# STM32SC1.net
KiCad netlist of a schematic drawn in EAGLE
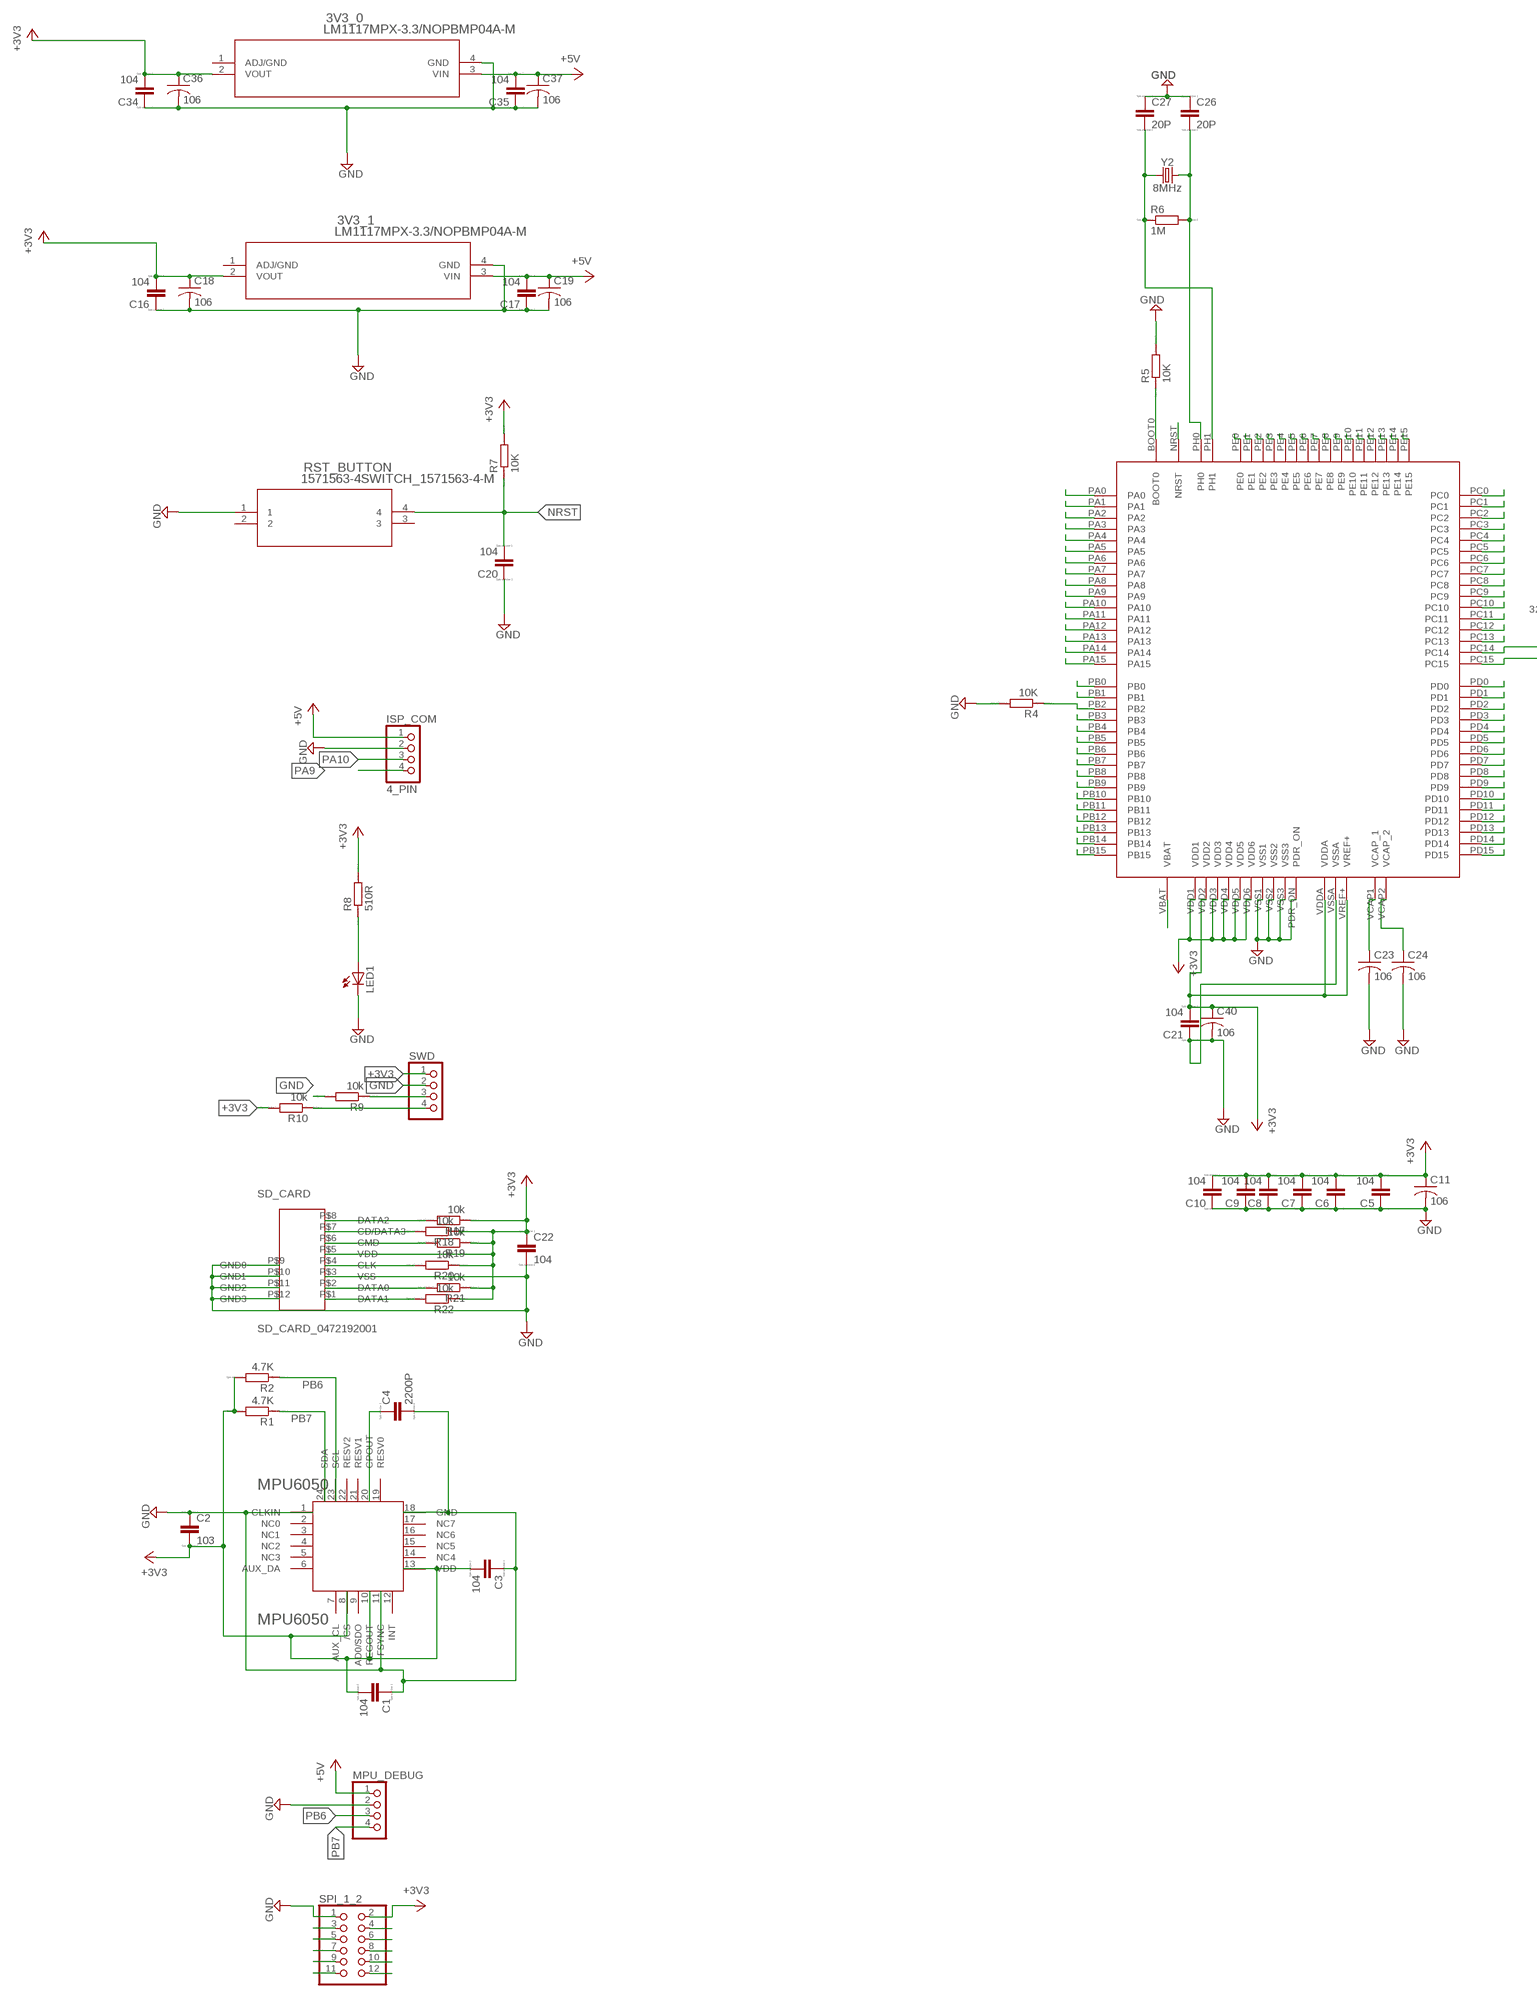
[diagram p0: schematic, sheet 1, part 1 of 2]
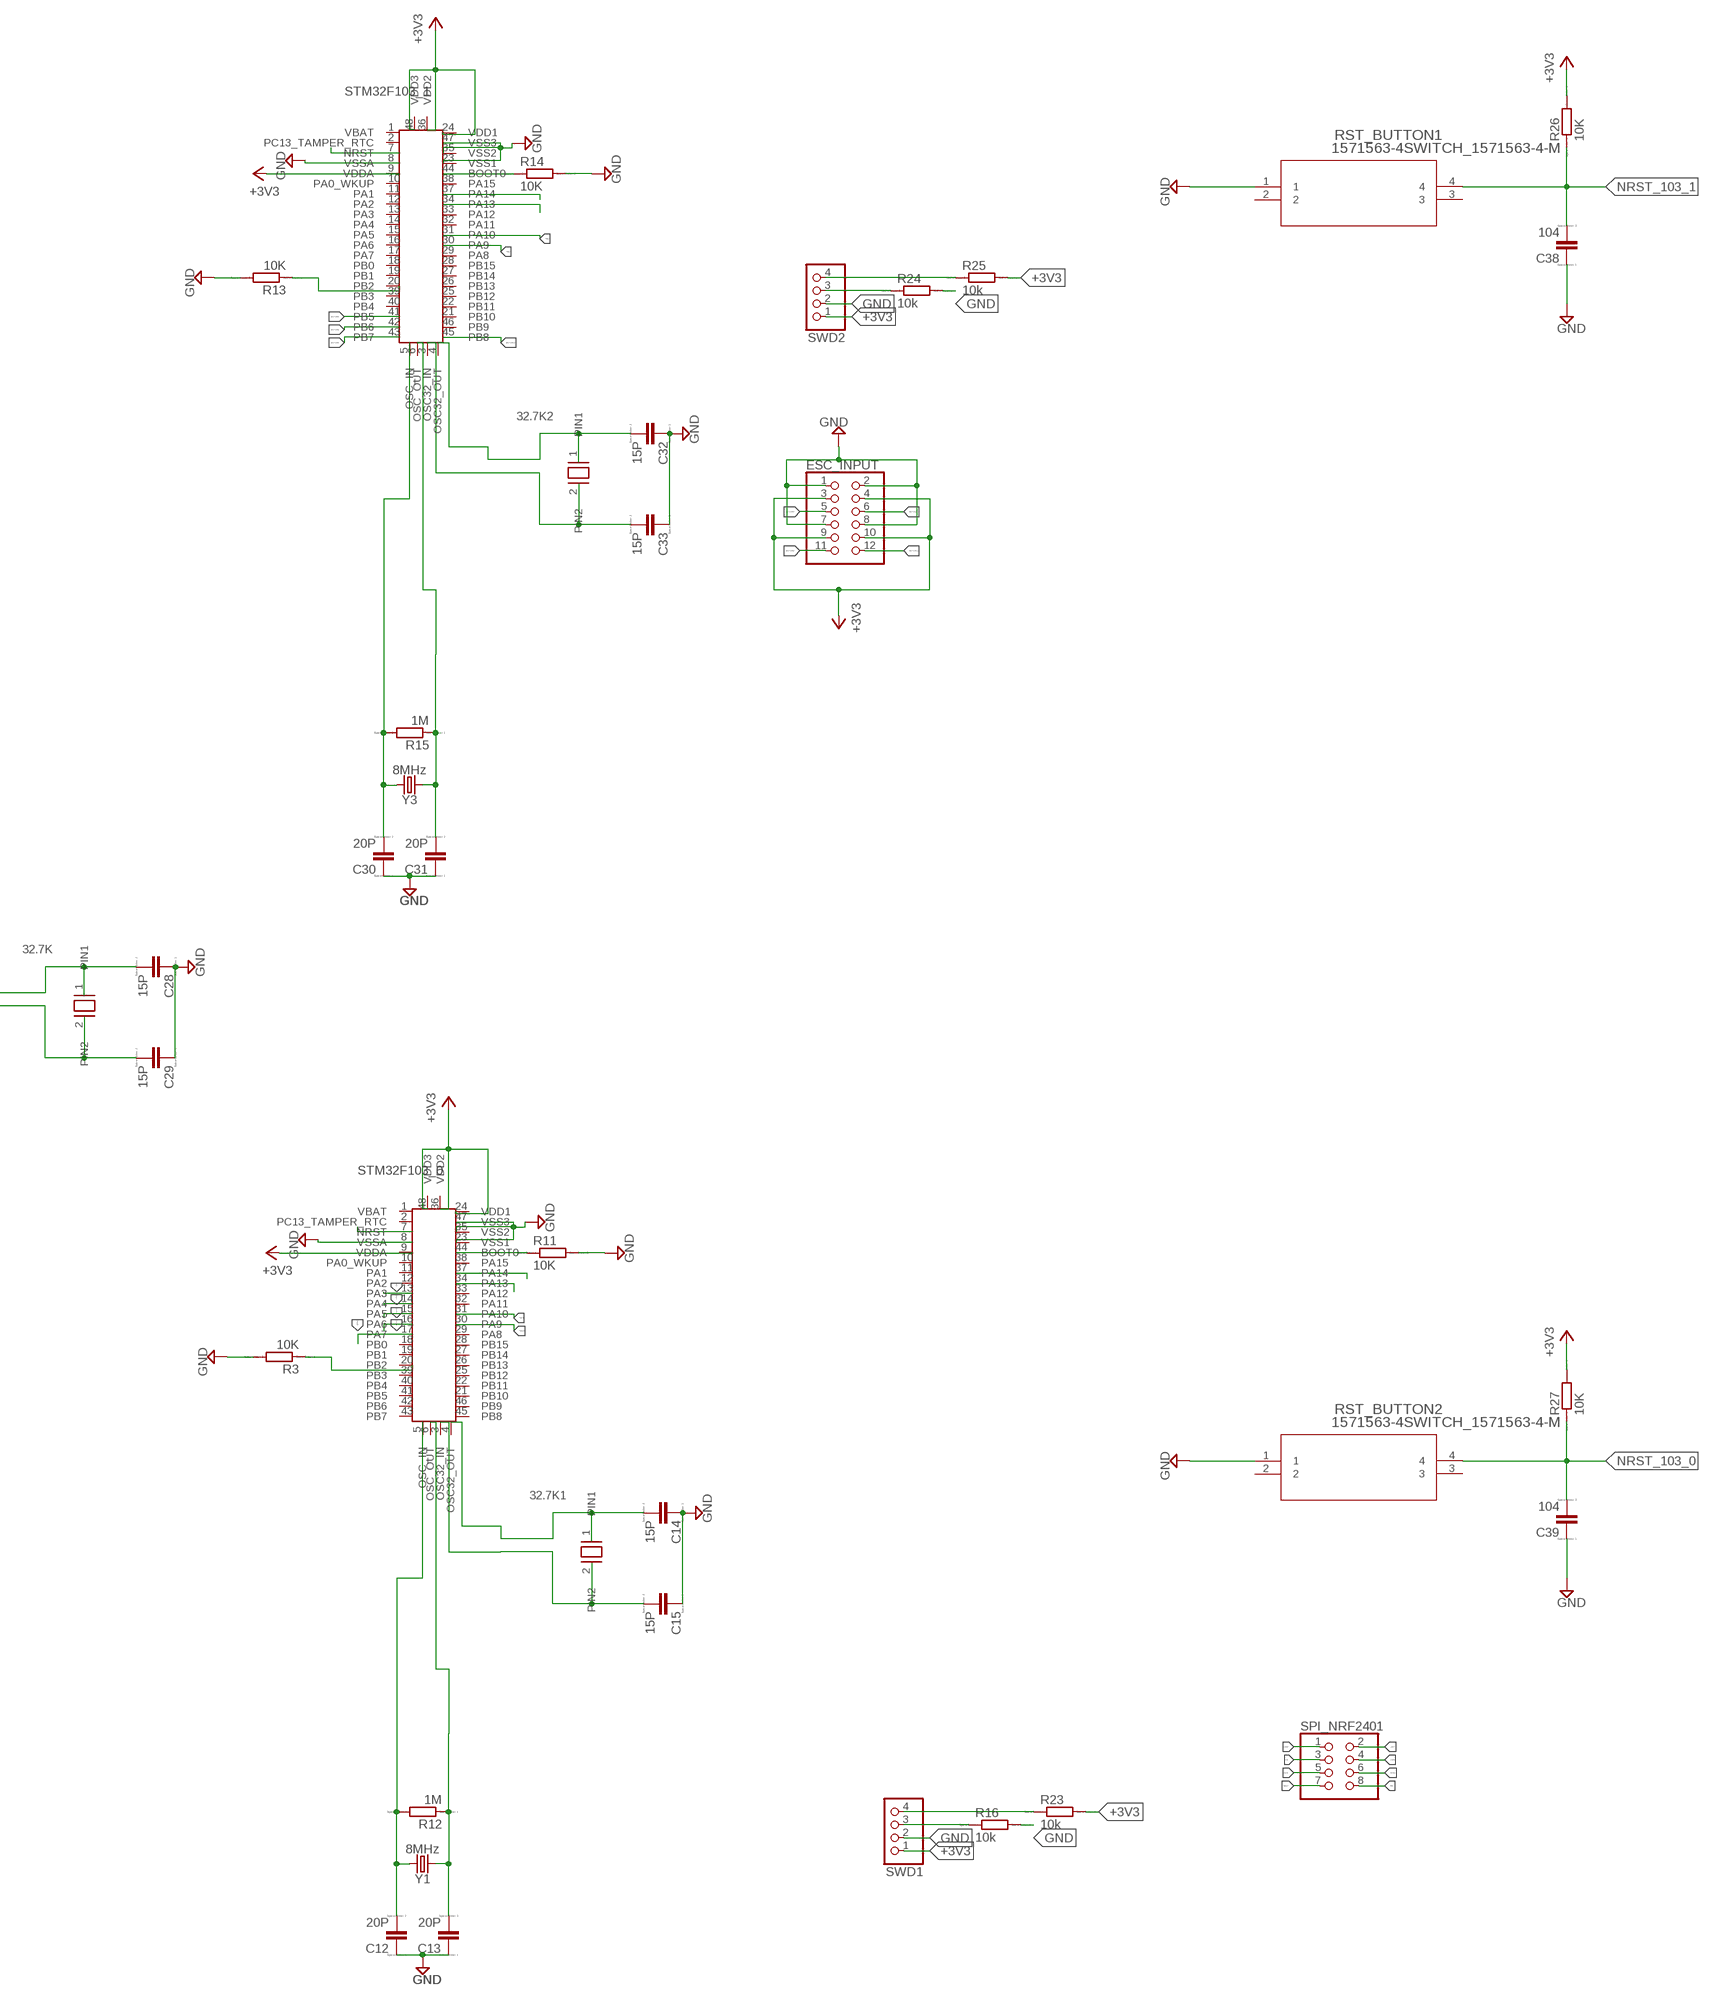
[diagram p1: schematic, sheet 1, part 2 of 2]

(export (version "E")
  (design (tool "Eeschema 10.0.6"))
  (components
    (comp (ref "3V3_0")
      (value "LM1117MPX-3.3/NOPBMP04A-M")
      (footprint "eagle-import:MP04A-M")
      (fields (field (name "MANUFACTURER_PART_NUMBER") "LM1117MPX3.3NOPB"))
      (libsource (lib "eagle-import") (part "LM1117MPX-3.3/NOPBMP04A-M"))
    )
    (comp (ref "3V3_1")
      (value "LM1117MPX-3.3/NOPBMP04A-M")
      (footprint "eagle-import:MP04A-M")
      (fields (field (name "MANUFACTURER_PART_NUMBER") "LM1117MPX3.3NOPB"))
      (libsource (lib "eagle-import") (part "LM1117MPX-3.3/NOPBMP04A-M"))
    )
    (comp (ref "32.7K")
      (value "CM315D")
      (footprint "eagle-import:CM315D_32.7K")
      (libsource (lib "eagle-import") (part "CM315D"))
    )
    (comp (ref "32.7K1")
      (value "CM315D")
      (footprint "eagle-import:CM315D_32.7K")
      (libsource (lib "eagle-import") (part "CM315D"))
    )
    (comp (ref "32.7K2")
      (value "CM315D")
      (footprint "eagle-import:CM315D_32.7K")
      (libsource (lib "eagle-import") (part "CM315D"))
    )
    (comp (ref "C1")
      (value "104")
      (footprint "eagle-import:C0603")
      (libsource (lib "eagle-import") (part "CC0603"))
    )
    (comp (ref "C2")
      (value "103")
      (footprint "eagle-import:C0603")
      (libsource (lib "eagle-import") (part "CC0603"))
    )
    (comp (ref "C3")
      (value "104")
      (footprint "eagle-import:C0603")
      (libsource (lib "eagle-import") (part "CC0603"))
    )
    (comp (ref "C4")
      (value "2200P")
      (footprint "eagle-import:C0603")
      (libsource (lib "eagle-import") (part "CC0603"))
    )
    (comp (ref "C5")
      (value "104")
      (footprint "eagle-import:C0603")
      (libsource (lib "eagle-import") (part "CC0603"))
    )
    (comp (ref "C6")
      (value "104")
      (footprint "eagle-import:C0603")
      (libsource (lib "eagle-import") (part "CC0603"))
    )
    (comp (ref "C7")
      (value "104")
      (footprint "eagle-import:C0603")
      (libsource (lib "eagle-import") (part "CC0603"))
    )
    (comp (ref "C8")
      (value "104")
      (footprint "eagle-import:C0603")
      (libsource (lib "eagle-import") (part "CC0603"))
    )
    (comp (ref "C9")
      (value "104")
      (footprint "eagle-import:C0603")
      (libsource (lib "eagle-import") (part "CC0603"))
    )
    (comp (ref "C10")
      (value "104")
      (footprint "eagle-import:C0603")
      (libsource (lib "eagle-import") (part "CC0603"))
    )
    (comp (ref "C11")
      (value "106")
      (footprint "eagle-import:C0805")
      (libsource (lib "eagle-import") (part "C-USC0805"))
    )
    (comp (ref "C12")
      (value "20P")
      (footprint "eagle-import:C0603")
      (libsource (lib "eagle-import") (part "CC0603"))
    )
    (comp (ref "C13")
      (value "20P")
      (footprint "eagle-import:C0603")
      (libsource (lib "eagle-import") (part "CC0603"))
    )
    (comp (ref "C14")
      (value "15P")
      (footprint "eagle-import:C0603")
      (libsource (lib "eagle-import") (part "CC0603"))
    )
    (comp (ref "C15")
      (value "15P")
      (footprint "eagle-import:C0603")
      (libsource (lib "eagle-import") (part "CC0603"))
    )
    (comp (ref "C16")
      (value "104")
      (footprint "eagle-import:C0603")
      (libsource (lib "eagle-import") (part "CC0603"))
    )
    (comp (ref "C17")
      (value "104")
      (footprint "eagle-import:C0603")
      (libsource (lib "eagle-import") (part "CC0603"))
    )
    (comp (ref "C18")
      (value "106")
      (footprint "eagle-import:C0805")
      (libsource (lib "eagle-import") (part "C-USC0805"))
    )
    (comp (ref "C19")
      (value "106")
      (footprint "eagle-import:C0805")
      (libsource (lib "eagle-import") (part "C-USC0805"))
    )
    (comp (ref "C20")
      (value "104")
      (footprint "eagle-import:C0603")
      (libsource (lib "eagle-import") (part "CC0603"))
    )
    (comp (ref "C21")
      (value "104")
      (footprint "eagle-import:C0603")
      (libsource (lib "eagle-import") (part "CC0603"))
    )
    (comp (ref "C22")
      (value "104")
      (footprint "eagle-import:C0603")
      (libsource (lib "eagle-import") (part "CC0603"))
    )
    (comp (ref "C23")
      (value "106")
      (footprint "eagle-import:C0805")
      (libsource (lib "eagle-import") (part "C-USC0805"))
    )
    (comp (ref "C24")
      (value "106")
      (footprint "eagle-import:C0805")
      (libsource (lib "eagle-import") (part "C-USC0805"))
    )
    (comp (ref "C26")
      (value "20P")
      (footprint "eagle-import:C0603")
      (libsource (lib "eagle-import") (part "CC0603"))
    )
    (comp (ref "C27")
      (value "20P")
      (footprint "eagle-import:C0603")
      (libsource (lib "eagle-import") (part "CC0603"))
    )
    (comp (ref "C28")
      (value "15P")
      (footprint "eagle-import:C0603")
      (libsource (lib "eagle-import") (part "CC0603"))
    )
    (comp (ref "C29")
      (value "15P")
      (footprint "eagle-import:C0603")
      (libsource (lib "eagle-import") (part "CC0603"))
    )
    (comp (ref "C30")
      (value "20P")
      (footprint "eagle-import:C0603")
      (libsource (lib "eagle-import") (part "CC0603"))
    )
    (comp (ref "C31")
      (value "20P")
      (footprint "eagle-import:C0603")
      (libsource (lib "eagle-import") (part "CC0603"))
    )
    (comp (ref "C32")
      (value "15P")
      (footprint "eagle-import:C0603")
      (libsource (lib "eagle-import") (part "CC0603"))
    )
    (comp (ref "C33")
      (value "15P")
      (footprint "eagle-import:C0603")
      (libsource (lib "eagle-import") (part "CC0603"))
    )
    (comp (ref "C34")
      (value "104")
      (footprint "eagle-import:C0603")
      (libsource (lib "eagle-import") (part "CC0603"))
    )
    (comp (ref "C35")
      (value "104")
      (footprint "eagle-import:C0603")
      (libsource (lib "eagle-import") (part "CC0603"))
    )
    (comp (ref "C36")
      (value "106")
      (footprint "eagle-import:C0805")
      (libsource (lib "eagle-import") (part "C-USC0805"))
    )
    (comp (ref "C37")
      (value "106")
      (footprint "eagle-import:C0805")
      (libsource (lib "eagle-import") (part "C-USC0805"))
    )
    (comp (ref "C38")
      (value "104")
      (footprint "eagle-import:C0603")
      (libsource (lib "eagle-import") (part "CC0603"))
    )
    (comp (ref "C39")
      (value "104")
      (footprint "eagle-import:C0603")
      (libsource (lib "eagle-import") (part "CC0603"))
    )
    (comp (ref "C40")
      (value "106")
      (footprint "eagle-import:C0805")
      (libsource (lib "eagle-import") (part "C-USC0805"))
    )
    (comp (ref "ESC_INPUT")
      (value "PINHD-2X6/90")
      (footprint "eagle-import:2X06_90")
      (libsource (lib "eagle-import") (part "PINHD-2X6/90"))
    )
    (comp (ref "ISP_COM")
      (value "4_PIN")
      (footprint "eagle-import:1X04")
      (libsource (lib "eagle-import") (part "PINHD-1X4"))
    )
    (comp (ref "LED1")
      (value "LEDCHIPLED_0805")
      (footprint "eagle-import:CHIPLED_0805")
      (libsource (lib "eagle-import") (part "LEDCHIPLED_0805"))
    )
    (comp (ref "MPU6050")
      (value "MPU6050")
      (footprint "eagle-import:MPU6050")
      (libsource (lib "eagle-import") (part "MPU6050"))
    )
    (comp (ref "MPU_DEBUG")
      (value "PINHD-1X4")
      (footprint "eagle-import:1X04")
      (libsource (lib "eagle-import") (part "PINHD-1X4"))
    )
    (comp (ref "R1")
      (value "4.7K")
      (footprint "eagle-import:R0603")
      (libsource (lib "eagle-import") (part "RR0603"))
    )
    (comp (ref "R2")
      (value "4.7K")
      (footprint "eagle-import:R0603")
      (libsource (lib "eagle-import") (part "RR0603"))
    )
    (comp (ref "R3")
      (value "10K")
      (footprint "eagle-import:R0603")
      (libsource (lib "eagle-import") (part "RR0603"))
    )
    (comp (ref "R4")
      (value "10K")
      (footprint "eagle-import:R0603")
      (libsource (lib "eagle-import") (part "RR0603"))
    )
    (comp (ref "R5")
      (value "10K")
      (footprint "eagle-import:R0603")
      (libsource (lib "eagle-import") (part "RR0603"))
    )
    (comp (ref "R6")
      (value "1M")
      (footprint "eagle-import:R0603")
      (libsource (lib "eagle-import") (part "RR0603"))
    )
    (comp (ref "R7")
      (value "10K")
      (footprint "eagle-import:R0603")
      (libsource (lib "eagle-import") (part "RR0603"))
    )
    (comp (ref "R8")
      (value "510R")
      (footprint "eagle-import:R0603")
      (libsource (lib "eagle-import") (part "RR0603"))
    )
    (comp (ref "R9")
      (value "10k")
      (footprint "eagle-import:R0603")
      (libsource (lib "eagle-import") (part "RR0603"))
    )
    (comp (ref "R10")
      (value "10k")
      (footprint "eagle-import:R0603")
      (libsource (lib "eagle-import") (part "RR0603"))
    )
    (comp (ref "R11")
      (value "10K")
      (footprint "eagle-import:R0603")
      (libsource (lib "eagle-import") (part "RR0603"))
    )
    (comp (ref "R12")
      (value "1M")
      (footprint "eagle-import:R0603")
      (libsource (lib "eagle-import") (part "RR0603"))
    )
    (comp (ref "R13")
      (value "10K")
      (footprint "eagle-import:R0603")
      (libsource (lib "eagle-import") (part "RR0603"))
    )
    (comp (ref "R14")
      (value "10K")
      (footprint "eagle-import:R0603")
      (libsource (lib "eagle-import") (part "RR0603"))
    )
    (comp (ref "R15")
      (value "1M")
      (footprint "eagle-import:R0603")
      (libsource (lib "eagle-import") (part "RR0603"))
    )
    (comp (ref "R16")
      (value "10k")
      (footprint "eagle-import:R0603")
      (libsource (lib "eagle-import") (part "RR0603"))
    )
    (comp (ref "R17")
      (value "10k")
      (footprint "eagle-import:R0603")
      (libsource (lib "eagle-import") (part "RR0603"))
    )
    (comp (ref "R18")
      (value "10k")
      (footprint "eagle-import:R0603")
      (libsource (lib "eagle-import") (part "RR0603"))
    )
    (comp (ref "R19")
      (value "10k")
      (footprint "eagle-import:R0603")
      (libsource (lib "eagle-import") (part "RR0603"))
    )
    (comp (ref "R20")
      (value "10k")
      (footprint "eagle-import:R0603")
      (libsource (lib "eagle-import") (part "RR0603"))
    )
    (comp (ref "R21")
      (value "10k")
      (footprint "eagle-import:R0603")
      (libsource (lib "eagle-import") (part "RR0603"))
    )
    (comp (ref "R22")
      (value "10k")
      (footprint "eagle-import:R0603")
      (libsource (lib "eagle-import") (part "RR0603"))
    )
    (comp (ref "R23")
      (value "10k")
      (footprint "eagle-import:R0603")
      (libsource (lib "eagle-import") (part "RR0603"))
    )
    (comp (ref "R24")
      (value "10k")
      (footprint "eagle-import:R0603")
      (libsource (lib "eagle-import") (part "RR0603"))
    )
    (comp (ref "R25")
      (value "10k")
      (footprint "eagle-import:R0603")
      (libsource (lib "eagle-import") (part "RR0603"))
    )
    (comp (ref "R26")
      (value "10K")
      (footprint "eagle-import:R0603")
      (libsource (lib "eagle-import") (part "RR0603"))
    )
    (comp (ref "R27")
      (value "10K")
      (footprint "eagle-import:R0603")
      (libsource (lib "eagle-import") (part "RR0603"))
    )
    (comp (ref "RST_BUTTON")
      (value "1571563-4SWITCH_1571563-4-M")
      (footprint "eagle-import:SWITCH_1571563-4-M")
      (fields (field (name "MANUFACTURER_PART_NUMBER") "15715634"))
      (libsource (lib "eagle-import") (part "1571563-4SWITCH_1571563-4-M"))
    )
    (comp (ref "RST_BUTTON1")
      (value "1571563-4SWITCH_1571563-4-M")
      (footprint "eagle-import:SWITCH_1571563-4-M")
      (fields (field (name "MANUFACTURER_PART_NUMBER") "15715634"))
      (libsource (lib "eagle-import") (part "1571563-4SWITCH_1571563-4-M"))
    )
    (comp (ref "RST_BUTTON2")
      (value "1571563-4SWITCH_1571563-4-M")
      (footprint "eagle-import:SWITCH_1571563-4-M")
      (fields (field (name "MANUFACTURER_PART_NUMBER") "15715634"))
      (libsource (lib "eagle-import") (part "1571563-4SWITCH_1571563-4-M"))
    )
    (comp (ref "SD_CARD")
      (value "SD_CARD_0472192001")
      (footprint "eagle-import:0472192001")
      (libsource (lib "eagle-import") (part "SD_CARD_0472192001"))
    )
    (comp (ref "SPI_1_2")
      (value "PINHD-2X6/90")
      (footprint "eagle-import:2X06_90")
      (libsource (lib "eagle-import") (part "PINHD-2X6/90"))
    )
    (comp (ref "SPI_NRF2401")
      (value "PINHD-2X4")
      (footprint "eagle-import:2X04")
      (libsource (lib "eagle-import") (part "PINHD-2X4"))
    )
    (comp (ref "STM32F103_0")
      (value "STM32F103C8T6")
      (footprint "eagle-import:STM32103C8T6_LQFP48")
      (libsource (lib "eagle-import") (part "STM32F103C8T6"))
    )
    (comp (ref "STM32F103_1")
      (value "STM32F103C8T6")
      (footprint "eagle-import:STM32103C8T6_LQFP48")
      (libsource (lib "eagle-import") (part "STM32F103C8T6"))
    )
    (comp (ref "SWD")
      (value "PINHD-1X4")
      (footprint "eagle-import:1X04")
      (libsource (lib "eagle-import") (part "PINHD-1X4"))
    )
    (comp (ref "SWD1")
      (value "PINHD-1X4")
      (footprint "eagle-import:1X04")
      (libsource (lib "eagle-import") (part "PINHD-1X4"))
    )
    (comp (ref "SWD2")
      (value "PINHD-1X4")
      (footprint "eagle-import:1X04")
      (libsource (lib "eagle-import") (part "PINHD-1X4"))
    )
    (comp (ref "U$1")
      (value "STM32F4V_100PIN_GENERIC")
      (footprint "eagle-import:LQFP100")
      (libsource (lib "eagle-import") (part "STM32F4V_100PIN_GENERIC"))
    )
    (comp (ref "Y1")
      (value "8MHz")
      (footprint "eagle-import:HC49UP")
      (libsource (lib "eagle-import") (part "CRYSTAL-8MHZSMD-HC49UP"))
    )
    (comp (ref "Y2")
      (value "8MHz")
      (footprint "eagle-import:HC49UP")
      (libsource (lib "eagle-import") (part "CRYSTAL-8MHZSMD-HC49UP"))
    )
    (comp (ref "Y3")
      (value "8MHz")
      (footprint "eagle-import:HC49UP")
      (libsource (lib "eagle-import") (part "CRYSTAL-8MHZSMD-HC49UP"))
    )
  )
  (nets
    (net (code "1") (name "+3V3") (class "Default")
      (node (ref "3V3_0") (pin "2") (pinfunction "VOUT_2") (pintype "passive"))
      (node (ref "3V3_1") (pin "2") (pinfunction "VOUT_2") (pintype "passive"))
      (node (ref "C1") (pin "2") (pinfunction "2_2") (pintype "passive"))
      (node (ref "C10") (pin "2") (pinfunction "2_2") (pintype "passive"))
      (node (ref "C11") (pin "1") (pinfunction "1_1") (pintype "passive"))
      (node (ref "C16") (pin "2") (pinfunction "2_2") (pintype "passive"))
      (node (ref "C18") (pin "1") (pinfunction "1_1") (pintype "passive"))
      (node (ref "C2") (pin "2") (pinfunction "2_2") (pintype "passive"))
      (node (ref "C21") (pin "2") (pinfunction "2_2") (pintype "passive"))
      (node (ref "C22") (pin "1") (pinfunction "1_1") (pintype "passive"))
      (node (ref "C3") (pin "2") (pinfunction "2_2") (pintype "passive"))
      (node (ref "C34") (pin "2") (pinfunction "2_2") (pintype "passive"))
      (node (ref "C36") (pin "1") (pinfunction "1_1") (pintype "passive"))
      (node (ref "C40") (pin "1") (pinfunction "1_1") (pintype "passive"))
      (node (ref "C5") (pin "2") (pinfunction "2_2") (pintype "passive"))
      (node (ref "C6") (pin "2") (pinfunction "2_2") (pintype "passive"))
      (node (ref "C7") (pin "2") (pinfunction "2_2") (pintype "passive"))
      (node (ref "C8") (pin "2") (pinfunction "2_2") (pintype "passive"))
      (node (ref "C9") (pin "2") (pinfunction "2_2") (pintype "passive"))
      (node (ref "ESC_INPUT") (pin "10") (pinfunction "10_10") (pintype "passive"))
      (node (ref "ESC_INPUT") (pin "3") (pinfunction "3_3") (pintype "passive"))
      (node (ref "ESC_INPUT") (pin "4") (pinfunction "4_4") (pintype "passive"))
      (node (ref "ESC_INPUT") (pin "9") (pinfunction "9_9") (pintype "passive"))
      (node (ref "MPU6050") (pin "10") (pinfunction "REGOUT_10") (pintype "bidirectional"))
      (node (ref "MPU6050") (pin "13") (pinfunction "VDD_13") (pintype "bidirectional"))
      (node (ref "MPU6050") (pin "8") (pinfunction "/CS_8") (pintype "bidirectional"))
      (node (ref "R1") (pin "2") (pinfunction "2_2") (pintype "passive"))
      (node (ref "R10") (pin "2") (pinfunction "2_2") (pintype "passive"))
      (node (ref "R17") (pin "1") (pinfunction "1_1") (pintype "passive"))
      (node (ref "R18") (pin "1") (pinfunction "1_1") (pintype "passive"))
      (node (ref "R19") (pin "1") (pinfunction "1_1") (pintype "passive"))
      (node (ref "R2") (pin "2") (pinfunction "2_2") (pintype "passive"))
      (node (ref "R20") (pin "1") (pinfunction "1_1") (pintype "passive"))
      (node (ref "R21") (pin "1") (pinfunction "1_1") (pintype "passive"))
      (node (ref "R22") (pin "1") (pinfunction "1_1") (pintype "passive"))
      (node (ref "R23") (pin "2") (pinfunction "2_2") (pintype "passive"))
      (node (ref "R25") (pin "2") (pinfunction "2_2") (pintype "passive"))
      (node (ref "R26") (pin "2") (pinfunction "2_2") (pintype "passive"))
      (node (ref "R27") (pin "2") (pinfunction "2_2") (pintype "passive"))
      (node (ref "R7") (pin "2") (pinfunction "2_2") (pintype "passive"))
      (node (ref "R8") (pin "2") (pinfunction "2_2") (pintype "passive"))
      (node (ref "SD_CARD") (pin "P$5") (pinfunction "VDD_P$5") (pintype "bidirectional"))
      (node (ref "SPI_1_2") (pin "2") (pinfunction "2_2") (pintype "passive"))
      (node (ref "SPI_NRF2401") (pin "2") (pinfunction "2_2") (pintype "passive"))
      (node (ref "STM32F103_0") (pin "24") (pinfunction "VDD1_24") (pintype "bidirectional"))
      (node (ref "STM32F103_0") (pin "36") (pinfunction "VDD2_36") (pintype "bidirectional"))
      (node (ref "STM32F103_0") (pin "48") (pinfunction "VDD3_48") (pintype "bidirectional"))
      (node (ref "STM32F103_0") (pin "9") (pinfunction "VDDA_9") (pintype "bidirectional"))
      (node (ref "STM32F103_1") (pin "24") (pinfunction "VDD1_24") (pintype "bidirectional"))
      (node (ref "STM32F103_1") (pin "36") (pinfunction "VDD2_36") (pintype "bidirectional"))
      (node (ref "STM32F103_1") (pin "48") (pinfunction "VDD3_48") (pintype "bidirectional"))
      (node (ref "STM32F103_1") (pin "9") (pinfunction "VDDA_9") (pintype "bidirectional"))
      (node (ref "SWD") (pin "1") (pinfunction "1_1") (pintype "passive"))
      (node (ref "SWD1") (pin "1") (pinfunction "1_1") (pintype "passive"))
      (node (ref "SWD2") (pin "1") (pinfunction "1_1") (pintype "passive"))
      (node (ref "U$1") (pin "VDD1") (pinfunction "VDD1_VDD1") (pintype "bidirectional"))
      (node (ref "U$1") (pin "VDD2") (pinfunction "VDD2_VDD2") (pintype "bidirectional"))
      (node (ref "U$1") (pin "VDD3") (pinfunction "VDD3_VDD3") (pintype "bidirectional"))
      (node (ref "U$1") (pin "VDD4") (pinfunction "VDD4_VDD4") (pintype "bidirectional"))
      (node (ref "U$1") (pin "VDD5") (pinfunction "VDD5_VDD5") (pintype "bidirectional"))
      (node (ref "U$1") (pin "VDD6") (pinfunction "VDD6_VDD6") (pintype "bidirectional"))
      (node (ref "U$1") (pin "VDDA") (pinfunction "VDDA_VDDA") (pintype "bidirectional"))
      (node (ref "U$1") (pin "VREF+") (pinfunction "VREF+_VREF+") (pintype "bidirectional"))
    )
    (net (code "2") (name "+5V") (class "Default")
      (node (ref "3V3_0") (pin "3") (pinfunction "VIN_3") (pintype "input"))
      (node (ref "3V3_1") (pin "3") (pinfunction "VIN_3") (pintype "input"))
      (node (ref "C17") (pin "2") (pinfunction "2_2") (pintype "passive"))
      (node (ref "C19") (pin "1") (pinfunction "1_1") (pintype "passive"))
      (node (ref "C35") (pin "2") (pinfunction "2_2") (pintype "passive"))
      (node (ref "C37") (pin "1") (pinfunction "1_1") (pintype "passive"))
      (node (ref "ISP_COM") (pin "1") (pinfunction "1_1") (pintype "passive"))
      (node (ref "MPU_DEBUG") (pin "1") (pinfunction "1_1") (pintype "passive"))
    )
    (net (code "3") (name "/PA5") (class "Default")
      (node (ref "SPI_1_2") (pin "7") (pinfunction "7_7") (pintype "passive"))
      (node (ref "U$1") (pin "PA5") (pinfunction "PA5_PA5") (pintype "bidirectional"))
    )
    (net (code "4") (name "/PA6") (class "Default")
      (node (ref "SPI_1_2") (pin "9") (pinfunction "9_9") (pintype "passive"))
      (node (ref "U$1") (pin "PA6") (pinfunction "PA6_PA6") (pintype "bidirectional"))
    )
    (net (code "5") (name "/PA7") (class "Default")
      (node (ref "SPI_1_2") (pin "11") (pinfunction "11_11") (pintype "passive"))
      (node (ref "U$1") (pin "PA7") (pinfunction "PA7_PA7") (pintype "bidirectional"))
    )
    (net (code "6") (name "/PA13") (class "Default")
      (node (ref "R10") (pin "1") (pinfunction "1_1") (pintype "passive"))
      (node (ref "SWD") (pin "4") (pinfunction "4_4") (pintype "passive"))
      (node (ref "U$1") (pin "PA13") (pinfunction "PA13_PA13") (pintype "bidirectional"))
    )
    (net (code "7") (name "/PA14") (class "Default")
      (node (ref "R9") (pin "1") (pinfunction "1_1") (pintype "passive"))
      (node (ref "SWD") (pin "3") (pinfunction "3_3") (pintype "passive"))
      (node (ref "U$1") (pin "PA14") (pinfunction "PA14_PA14") (pintype "bidirectional"))
    )
    (net (code "8") (name "/PB10") (class "Default")
      (node (ref "SPI_1_2") (pin "8") (pinfunction "8_8") (pintype "passive"))
      (node (ref "U$1") (pin "PB10") (pinfunction "PB10_PB10") (pintype "bidirectional"))
    )
    (net (code "9") (name "/PC2") (class "Default")
      (node (ref "SPI_1_2") (pin "10") (pinfunction "10_10") (pintype "passive"))
      (node (ref "U$1") (pin "PC2") (pinfunction "PC2_PC2") (pintype "bidirectional"))
    )
    (net (code "10") (name "/PC3") (class "Default")
      (node (ref "SPI_1_2") (pin "12") (pinfunction "12_12") (pintype "passive"))
      (node (ref "U$1") (pin "PC3") (pinfunction "PC3_PC3") (pintype "bidirectional"))
    )
    (net (code "11") (name "/PC4") (class "Default")
      (node (ref "SPI_1_2") (pin "3") (pinfunction "3_3") (pintype "passive"))
      (node (ref "U$1") (pin "PC4") (pinfunction "PC4_PC4") (pintype "bidirectional"))
    )
    (net (code "12") (name "/PC5") (class "Default")
      (node (ref "SPI_1_2") (pin "5") (pinfunction "5_5") (pintype "passive"))
      (node (ref "U$1") (pin "PC5") (pinfunction "PC5_PC5") (pintype "bidirectional"))
    )
    (net (code "13") (name "/PC8") (class "Default")
      (node (ref "R21") (pin "2") (pinfunction "2_2") (pintype "passive"))
      (node (ref "SD_CARD") (pin "P$2") (pinfunction "DATA0_P$2") (pintype "bidirectional"))
      (node (ref "U$1") (pin "PC8") (pinfunction "PC8_PC8") (pintype "bidirectional"))
    )
    (net (code "14") (name "/PC9") (class "Default")
      (node (ref "R22") (pin "2") (pinfunction "2_2") (pintype "passive"))
      (node (ref "SD_CARD") (pin "P$1") (pinfunction "DATA1_P$1") (pintype "bidirectional"))
      (node (ref "U$1") (pin "PC9") (pinfunction "PC9_PC9") (pintype "bidirectional"))
    )
    (net (code "15") (name "/PC10") (class "Default")
      (node (ref "R17") (pin "2") (pinfunction "2_2") (pintype "passive"))
      (node (ref "SD_CARD") (pin "P$8") (pinfunction "DATA2_P$8") (pintype "bidirectional"))
      (node (ref "U$1") (pin "PC10") (pinfunction "PC10_PC10") (pintype "bidirectional"))
    )
    (net (code "16") (name "/PC11") (class "Default")
      (node (ref "R18") (pin "2") (pinfunction "2_2") (pintype "passive"))
      (node (ref "SD_CARD") (pin "P$7") (pinfunction "CD/DATA3_P$7") (pintype "bidirectional"))
      (node (ref "U$1") (pin "PC11") (pinfunction "PC11_PC11") (pintype "bidirectional"))
    )
    (net (code "17") (name "/PC12") (class "Default")
      (node (ref "R20") (pin "2") (pinfunction "2_2") (pintype "passive"))
      (node (ref "SD_CARD") (pin "P$4") (pinfunction "CLK_P$4") (pintype "bidirectional"))
      (node (ref "U$1") (pin "PC12") (pinfunction "PC12_PC12") (pintype "bidirectional"))
    )
    (net (code "18") (name "/PD2") (class "Default")
      (node (ref "R19") (pin "2") (pinfunction "2_2") (pintype "passive"))
      (node (ref "SD_CARD") (pin "P$6") (pinfunction "CMD_P$6") (pintype "bidirectional"))
      (node (ref "U$1") (pin "PD2") (pinfunction "PD2_PD2") (pintype "bidirectional"))
    )
    (net (code "19") (name "/PE7") (class "Default")
      (node (ref "SPI_1_2") (pin "4") (pinfunction "4_4") (pintype "passive"))
      (node (ref "U$1") (pin "PE7") (pinfunction "PE7_PE7") (pintype "bidirectional"))
    )
    (net (code "20") (name "/PE8") (class "Default")
      (node (ref "SPI_1_2") (pin "6") (pinfunction "6_6") (pintype "passive"))
      (node (ref "U$1") (pin "PE8") (pinfunction "PE8_PE8") (pintype "bidirectional"))
    )
    (net (code "21") (name "/SWCLK_103_0") (class "Default")
      (node (ref "R16") (pin "1") (pinfunction "1_1") (pintype "passive"))
      (node (ref "STM32F103_0") (pin "37") (pinfunction "PA14_37") (pintype "bidirectional"))
      (node (ref "SWD1") (pin "3") (pinfunction "3_3") (pintype "passive"))
    )
    (net (code "22") (name "/SWCLK_103_1") (class "Default")
      (node (ref "R24") (pin "1") (pinfunction "1_1") (pintype "passive"))
      (node (ref "STM32F103_1") (pin "37") (pinfunction "PA14_37") (pintype "bidirectional"))
      (node (ref "SWD2") (pin "3") (pinfunction "3_3") (pintype "passive"))
    )
    (net (code "23") (name "/SWDIO_103_0") (class "Default")
      (node (ref "R23") (pin "1") (pinfunction "1_1") (pintype "passive"))
      (node (ref "STM32F103_0") (pin "34") (pinfunction "PA13_34") (pintype "bidirectional"))
      (node (ref "SWD1") (pin "4") (pinfunction "4_4") (pintype "passive"))
    )
    (net (code "24") (name "/SWDIO_103_1") (class "Default")
      (node (ref "R25") (pin "1") (pinfunction "1_1") (pintype "passive"))
      (node (ref "STM32F103_1") (pin "34") (pinfunction "PA13_34") (pintype "bidirectional"))
      (node (ref "SWD2") (pin "4") (pinfunction "4_4") (pintype "passive"))
    )
    (net (code "25") (name "CE") (class "Default")
      (node (ref "SPI_NRF2401") (pin "3") (pinfunction "3_3") (pintype "passive"))
      (node (ref "STM32F103_0") (pin "13") (pinfunction "PA3_13") (pintype "bidirectional"))
    )
    (net (code "26") (name "CSN") (class "Default")
      (node (ref "SPI_NRF2401") (pin "4") (pinfunction "4_4") (pintype "passive"))
      (node (ref "STM32F103_0") (pin "14") (pinfunction "PA4_14") (pintype "bidirectional"))
    )
    (net (code "27") (name "GND") (class "Default")
      (node (ref "3V3_0") (pin "4") (pinfunction "GND_4") (pintype "power_in"))
      (node (ref "3V3_1") (pin "4") (pinfunction "GND_4") (pintype "power_in"))
      (node (ref "C1") (pin "1") (pinfunction "1_1") (pintype "passive"))
      (node (ref "C10") (pin "1") (pinfunction "1_1") (pintype "passive"))
      (node (ref "C11") (pin "2") (pinfunction "2_2") (pintype "passive"))
      (node (ref "C12") (pin "1") (pinfunction "1_1") (pintype "passive"))
      (node (ref "C13") (pin "1") (pinfunction "1_1") (pintype "passive"))
      (node (ref "C14") (pin "1") (pinfunction "1_1") (pintype "passive"))
      (node (ref "C15") (pin "1") (pinfunction "1_1") (pintype "passive"))
      (node (ref "C16") (pin "1") (pinfunction "1_1") (pintype "passive"))
      (node (ref "C17") (pin "1") (pinfunction "1_1") (pintype "passive"))
      (node (ref "C18") (pin "2") (pinfunction "2_2") (pintype "passive"))
      (node (ref "C19") (pin "2") (pinfunction "2_2") (pintype "passive"))
      (node (ref "C2") (pin "1") (pinfunction "1_1") (pintype "passive"))
      (node (ref "C20") (pin "1") (pinfunction "1_1") (pintype "passive"))
      (node (ref "C21") (pin "1") (pinfunction "1_1") (pintype "passive"))
      (node (ref "C22") (pin "2") (pinfunction "2_2") (pintype "passive"))
      (node (ref "C23") (pin "2") (pinfunction "2_2") (pintype "passive"))
      (node (ref "C24") (pin "2") (pinfunction "2_2") (pintype "passive"))
      (node (ref "C26") (pin "1") (pinfunction "1_1") (pintype "passive"))
      (node (ref "C27") (pin "1") (pinfunction "1_1") (pintype "passive"))
      (node (ref "C28") (pin "1") (pinfunction "1_1") (pintype "passive"))
      (node (ref "C29") (pin "1") (pinfunction "1_1") (pintype "passive"))
      (node (ref "C3") (pin "1") (pinfunction "1_1") (pintype "passive"))
      (node (ref "C30") (pin "1") (pinfunction "1_1") (pintype "passive"))
      (node (ref "C31") (pin "1") (pinfunction "1_1") (pintype "passive"))
      (node (ref "C32") (pin "1") (pinfunction "1_1") (pintype "passive"))
      (node (ref "C33") (pin "1") (pinfunction "1_1") (pintype "passive"))
      (node (ref "C34") (pin "1") (pinfunction "1_1") (pintype "passive"))
      (node (ref "C35") (pin "1") (pinfunction "1_1") (pintype "passive"))
      (node (ref "C36") (pin "2") (pinfunction "2_2") (pintype "passive"))
      (node (ref "C37") (pin "2") (pinfunction "2_2") (pintype "passive"))
      (node (ref "C38") (pin "1") (pinfunction "1_1") (pintype "passive"))
      (node (ref "C39") (pin "1") (pinfunction "1_1") (pintype "passive"))
      (node (ref "C4") (pin "2") (pinfunction "2_2") (pintype "passive"))
      (node (ref "C40") (pin "2") (pinfunction "2_2") (pintype "passive"))
      (node (ref "C5") (pin "1") (pinfunction "1_1") (pintype "passive"))
      (node (ref "C6") (pin "1") (pinfunction "1_1") (pintype "passive"))
      (node (ref "C7") (pin "1") (pinfunction "1_1") (pintype "passive"))
      (node (ref "C8") (pin "1") (pinfunction "1_1") (pintype "passive"))
      (node (ref "C9") (pin "1") (pinfunction "1_1") (pintype "passive"))
      (node (ref "ESC_INPUT") (pin "1") (pinfunction "1_1") (pintype "passive"))
      (node (ref "ESC_INPUT") (pin "2") (pinfunction "2_2") (pintype "passive"))
      (node (ref "ESC_INPUT") (pin "7") (pinfunction "7_7") (pintype "passive"))
      (node (ref "ESC_INPUT") (pin "8") (pinfunction "8_8") (pintype "passive"))
      (node (ref "ISP_COM") (pin "2") (pinfunction "2_2") (pintype "passive"))
      (node (ref "LED1") (pin "C") (pinfunction "C_C") (pintype "passive"))
      (node (ref "MPU6050") (pin "1") (pinfunction "CLKIN_1") (pintype "bidirectional"))
      (node (ref "MPU6050") (pin "11") (pinfunction "FSYNC_11") (pintype "bidirectional"))
      (node (ref "MPU6050") (pin "18") (pinfunction "GND_18") (pintype "bidirectional"))
      (node (ref "MPU_DEBUG") (pin "2") (pinfunction "2_2") (pintype "passive"))
      (node (ref "R11") (pin "2") (pinfunction "2_2") (pintype "passive"))
      (node (ref "R13") (pin "2") (pinfunction "2_2") (pintype "passive"))
      (node (ref "R14") (pin "2") (pinfunction "2_2") (pintype "passive"))
      (node (ref "R16") (pin "2") (pinfunction "2_2") (pintype "passive"))
      (node (ref "R24") (pin "2") (pinfunction "2_2") (pintype "passive"))
      (node (ref "R3") (pin "2") (pinfunction "2_2") (pintype "passive"))
      (node (ref "R4") (pin "2") (pinfunction "2_2") (pintype "passive"))
      (node (ref "R5") (pin "2") (pinfunction "2_2") (pintype "passive"))
      (node (ref "R9") (pin "2") (pinfunction "2_2") (pintype "passive"))
      (node (ref "RST_BUTTON") (pin "1") (pinfunction "1_1") (pintype "passive"))
      (node (ref "RST_BUTTON1") (pin "1") (pinfunction "1_1") (pintype "passive"))
      (node (ref "RST_BUTTON2") (pin "1") (pinfunction "1_1") (pintype "passive"))
      (node (ref "SD_CARD") (pin "P$10") (pinfunction "GND1_P$10") (pintype "bidirectional"))
      (node (ref "SD_CARD") (pin "P$11") (pinfunction "GND2_P$11") (pintype "bidirectional"))
      (node (ref "SD_CARD") (pin "P$12") (pinfunction "GND3_P$12") (pintype "bidirectional"))
      (node (ref "SD_CARD") (pin "P$3") (pinfunction "VSS_P$3") (pintype "bidirectional"))
      (node (ref "SD_CARD") (pin "P$9") (pinfunction "GND0_P$9") (pintype "bidirectional"))
      (node (ref "SPI_1_2") (pin "1") (pinfunction "1_1") (pintype "passive"))
      (node (ref "SPI_NRF2401") (pin "1") (pinfunction "1_1") (pintype "passive"))
      (node (ref "STM32F103_0") (pin "23") (pinfunction "VSS1_23") (pintype "bidirectional"))
      (node (ref "STM32F103_0") (pin "35") (pinfunction "VSS2_35") (pintype "bidirectional"))
      (node (ref "STM32F103_0") (pin "47") (pinfunction "VSS3_47") (pintype "bidirectional"))
      (node (ref "STM32F103_0") (pin "8") (pinfunction "VSSA_8") (pintype "bidirectional"))
      (node (ref "STM32F103_1") (pin "23") (pinfunction "VSS1_23") (pintype "bidirectional"))
      (node (ref "STM32F103_1") (pin "35") (pinfunction "VSS2_35") (pintype "bidirectional"))
      (node (ref "STM32F103_1") (pin "47") (pinfunction "VSS3_47") (pintype "bidirectional"))
      (node (ref "STM32F103_1") (pin "8") (pinfunction "VSSA_8") (pintype "bidirectional"))
      (node (ref "SWD") (pin "2") (pinfunction "2_2") (pintype "passive"))
      (node (ref "SWD1") (pin "2") (pinfunction "2_2") (pintype "passive"))
      (node (ref "SWD2") (pin "2") (pinfunction "2_2") (pintype "passive"))
      (node (ref "U$1") (pin "PDR_ON") (pinfunction "PDR_ON_PDR_ON") (pintype "bidirectional"))
      (node (ref "U$1") (pin "VSS1") (pinfunction "VSS1_VSS1") (pintype "bidirectional"))
      (node (ref "U$1") (pin "VSS2") (pinfunction "VSS2_VSS2") (pintype "bidirectional"))
      (node (ref "U$1") (pin "VSS3") (pinfunction "VSS3_VSS3") (pintype "bidirectional"))
      (node (ref "U$1") (pin "VSSA") (pinfunction "VSSA_VSSA") (pintype "bidirectional"))
    )
    (net (code "28") (name "IRQ") (class "Default")
      (node (ref "SPI_NRF2401") (pin "8") (pinfunction "8_8") (pintype "passive"))
    )
    (net (code "29") (name "MISO") (class "Default")
      (node (ref "SPI_NRF2401") (pin "7") (pinfunction "7_7") (pintype "passive"))
      (node (ref "STM32F103_0") (pin "16") (pinfunction "PA6_16") (pintype "bidirectional"))
    )
    (net (code "30") (name "MOSI") (class "Default")
      (node (ref "SPI_NRF2401") (pin "6") (pinfunction "6_6") (pintype "passive"))
      (node (ref "STM32F103_0") (pin "17") (pinfunction "PA7_17") (pintype "bidirectional"))
    )
    (net (code "31") (name "MOTOR1") (class "Default")
      (node (ref "ESC_INPUT") (pin "5") (pinfunction "5_5") (pintype "passive"))
      (node (ref "STM32F103_1") (pin "41") (pinfunction "PB5_41") (pintype "bidirectional"))
    )
    (net (code "32") (name "MOTOR2") (class "Default")
      (node (ref "ESC_INPUT") (pin "11") (pinfunction "11_11") (pintype "passive"))
      (node (ref "STM32F103_1") (pin "42") (pinfunction "PB6_42") (pintype "bidirectional"))
    )
    (net (code "33") (name "MOTOR3") (class "Default")
      (node (ref "ESC_INPUT") (pin "6") (pinfunction "6_6") (pintype "passive"))
      (node (ref "STM32F103_1") (pin "43") (pinfunction "PB7_43") (pintype "bidirectional"))
    )
    (net (code "34") (name "MOTOR4") (class "Default")
      (node (ref "ESC_INPUT") (pin "12") (pinfunction "12_12") (pintype "passive"))
      (node (ref "STM32F103_1") (pin "45") (pinfunction "PB8_45") (pintype "bidirectional"))
    )
    (net (code "35") (name "NRST") (class "Default")
      (node (ref "C20") (pin "2") (pinfunction "2_2") (pintype "passive"))
      (node (ref "R7") (pin "1") (pinfunction "1_1") (pintype "passive"))
      (node (ref "RST_BUTTON") (pin "4") (pinfunction "4_4") (pintype "passive"))
      (node (ref "U$1") (pin "NRST") (pinfunction "NRST_NRST") (pintype "bidirectional"))
    )
    (net (code "36") (name "NRST_103_0") (class "Default")
      (node (ref "C39") (pin "2") (pinfunction "2_2") (pintype "passive"))
      (node (ref "R27") (pin "1") (pinfunction "1_1") (pintype "passive"))
      (node (ref "RST_BUTTON2") (pin "4") (pinfunction "4_4") (pintype "passive"))
      (node (ref "STM32F103_0") (pin "7") (pinfunction "NRST_7") (pintype "bidirectional"))
    )
    (net (code "37") (name "NRST_103_1") (class "Default")
      (node (ref "C38") (pin "2") (pinfunction "2_2") (pintype "passive"))
      (node (ref "R26") (pin "1") (pinfunction "1_1") (pintype "passive"))
      (node (ref "RST_BUTTON1") (pin "4") (pinfunction "4_4") (pintype "passive"))
      (node (ref "STM32F103_1") (pin "7") (pinfunction "NRST_7") (pintype "bidirectional"))
    )
    (net (code "38") (name "Net-(32.7K-PIN1)") (class "Default")
      (node (ref "32.7K") (pin "1") (pinfunction "PIN1_1") (pintype "bidirectional"))
      (node (ref "C28") (pin "2") (pinfunction "2_2") (pintype "passive"))
      (node (ref "U$1") (pin "PC14") (pinfunction "PC14_PC14") (pintype "bidirectional"))
    )
    (net (code "39") (name "Net-(32.7K-PIN2)") (class "Default")
      (node (ref "32.7K") (pin "2") (pinfunction "PIN2_2") (pintype "bidirectional"))
      (node (ref "C29") (pin "2") (pinfunction "2_2") (pintype "passive"))
      (node (ref "U$1") (pin "PC15") (pinfunction "PC15_PC15") (pintype "bidirectional"))
    )
    (net (code "40") (name "Net-(32.7K1-PIN1)") (class "Default")
      (node (ref "32.7K1") (pin "1") (pinfunction "PIN1_1") (pintype "bidirectional"))
      (node (ref "C14") (pin "2") (pinfunction "2_2") (pintype "passive"))
      (node (ref "STM32F103_0") (pin "4") (pinfunction "OSC32_OUT_4") (pintype "bidirectional"))
    )
    (net (code "41") (name "Net-(32.7K1-PIN2)") (class "Default")
      (node (ref "32.7K1") (pin "2") (pinfunction "PIN2_2") (pintype "bidirectional"))
      (node (ref "C15") (pin "2") (pinfunction "2_2") (pintype "passive"))
      (node (ref "STM32F103_0") (pin "3") (pinfunction "OSC32_IN_3") (pintype "bidirectional"))
    )
    (net (code "42") (name "Net-(32.7K2-PIN1)") (class "Default")
      (node (ref "32.7K2") (pin "1") (pinfunction "PIN1_1") (pintype "bidirectional"))
      (node (ref "C32") (pin "2") (pinfunction "2_2") (pintype "passive"))
      (node (ref "STM32F103_1") (pin "4") (pinfunction "OSC32_OUT_4") (pintype "bidirectional"))
    )
    (net (code "43") (name "Net-(32.7K2-PIN2)") (class "Default")
      (node (ref "32.7K2") (pin "2") (pinfunction "PIN2_2") (pintype "bidirectional"))
      (node (ref "C33") (pin "2") (pinfunction "2_2") (pintype "passive"))
      (node (ref "STM32F103_1") (pin "3") (pinfunction "OSC32_IN_3") (pintype "bidirectional"))
    )
    (net (code "44") (name "Net-(C26-Pad2)") (class "Default")
      (node (ref "C26") (pin "2") (pinfunction "2_2") (pintype "passive"))
      (node (ref "R6") (pin "2") (pinfunction "2_2") (pintype "passive"))
      (node (ref "U$1") (pin "PH0") (pinfunction "PH0_PH0") (pintype "bidirectional"))
      (node (ref "Y2") (pin "2") (pinfunction "2_2") (pintype "passive"))
    )
    (net (code "45") (name "Net-(C27-Pad2)") (class "Default")
      (node (ref "C27") (pin "2") (pinfunction "2_2") (pintype "passive"))
      (node (ref "R6") (pin "1") (pinfunction "1_1") (pintype "passive"))
      (node (ref "U$1") (pin "PH1") (pinfunction "PH1_PH1") (pintype "bidirectional"))
      (node (ref "Y2") (pin "1") (pinfunction "1_1") (pintype "passive"))
    )
    (net (code "46") (name "Net-(LED1-PadA)") (class "Default")
      (node (ref "LED1") (pin "A") (pinfunction "A_A") (pintype "passive"))
      (node (ref "R8") (pin "1") (pinfunction "1_1") (pintype "passive"))
    )
    (net (code "47") (name "Net-(MPU6050-CPOUT)") (class "Default")
      (node (ref "C4") (pin "1") (pinfunction "1_1") (pintype "passive"))
      (node (ref "MPU6050") (pin "20") (pinfunction "CPOUT_20") (pintype "bidirectional"))
    )
    (net (code "48") (name "Net-(R4-Pad1)") (class "Default")
      (node (ref "R4") (pin "1") (pinfunction "1_1") (pintype "passive"))
      (node (ref "U$1") (pin "PB2") (pinfunction "PB2_PB2") (pintype "bidirectional"))
    )
    (net (code "49") (name "Net-(R5-Pad1)") (class "Default")
      (node (ref "R5") (pin "1") (pinfunction "1_1") (pintype "passive"))
      (node (ref "U$1") (pin "BOOT0") (pinfunction "BOOT0_BOOT0") (pintype "bidirectional"))
    )
    (net (code "50") (name "Net-(STM32F103_0-BOOT0)") (class "Default")
      (node (ref "R11") (pin "1") (pinfunction "1_1") (pintype "passive"))
      (node (ref "STM32F103_0") (pin "44") (pinfunction "BOOT0_44") (pintype "bidirectional"))
    )
    (net (code "51") (name "Net-(STM32F103_0-OSC_IN)") (class "Default")
      (node (ref "C12") (pin "2") (pinfunction "2_2") (pintype "passive"))
      (node (ref "R12") (pin "2") (pinfunction "2_2") (pintype "passive"))
      (node (ref "STM32F103_0") (pin "5") (pinfunction "OSC_IN_5") (pintype "bidirectional"))
      (node (ref "Y1") (pin "2") (pinfunction "2_2") (pintype "passive"))
    )
    (net (code "52") (name "Net-(STM32F103_0-OSC_OUT)") (class "Default")
      (node (ref "C13") (pin "2") (pinfunction "2_2") (pintype "passive"))
      (node (ref "R12") (pin "1") (pinfunction "1_1") (pintype "passive"))
      (node (ref "STM32F103_0") (pin "6") (pinfunction "OSC_OUT_6") (pintype "bidirectional"))
      (node (ref "Y1") (pin "1") (pinfunction "1_1") (pintype "passive"))
    )
    (net (code "53") (name "Net-(STM32F103_0-PB2)") (class "Default")
      (node (ref "R3") (pin "1") (pinfunction "1_1") (pintype "passive"))
      (node (ref "STM32F103_0") (pin "20") (pinfunction "PB2_20") (pintype "bidirectional"))
    )
    (net (code "54") (name "Net-(STM32F103_1-BOOT0)") (class "Default")
      (node (ref "R14") (pin "1") (pinfunction "1_1") (pintype "passive"))
      (node (ref "STM32F103_1") (pin "44") (pinfunction "BOOT0_44") (pintype "bidirectional"))
    )
    (net (code "55") (name "Net-(STM32F103_1-OSC_IN)") (class "Default")
      (node (ref "C30") (pin "2") (pinfunction "2_2") (pintype "passive"))
      (node (ref "R15") (pin "2") (pinfunction "2_2") (pintype "passive"))
      (node (ref "STM32F103_1") (pin "5") (pinfunction "OSC_IN_5") (pintype "bidirectional"))
      (node (ref "Y3") (pin "2") (pinfunction "2_2") (pintype "passive"))
    )
    (net (code "56") (name "Net-(STM32F103_1-OSC_OUT)") (class "Default")
      (node (ref "C31") (pin "2") (pinfunction "2_2") (pintype "passive"))
      (node (ref "R15") (pin "1") (pinfunction "1_1") (pintype "passive"))
      (node (ref "STM32F103_1") (pin "6") (pinfunction "OSC_OUT_6") (pintype "bidirectional"))
      (node (ref "Y3") (pin "1") (pinfunction "1_1") (pintype "passive"))
    )
    (net (code "57") (name "Net-(STM32F103_1-PB2)") (class "Default")
      (node (ref "R13") (pin "1") (pinfunction "1_1") (pintype "passive"))
      (node (ref "STM32F103_1") (pin "20") (pinfunction "PB2_20") (pintype "bidirectional"))
    )
    (net (code "58") (name "Net-(U$1-VCAP_1)") (class "Default")
      (node (ref "C23") (pin "1") (pinfunction "1_1") (pintype "passive"))
      (node (ref "U$1") (pin "VCAP1") (pinfunction "VCAP_1_VCAP1") (pintype "bidirectional"))
    )
    (net (code "59") (name "Net-(U$1-VCAP_2)") (class "Default")
      (node (ref "C24") (pin "1") (pinfunction "1_1") (pintype "passive"))
      (node (ref "U$1") (pin "VCAP2") (pinfunction "VCAP_2_VCAP2") (pintype "bidirectional"))
    )
    (net (code "60") (name "PA2") (class "Default")
      (node (ref "STM32F103_1") (pin "31") (pinfunction "PA10_31") (pintype "bidirectional"))
      (node (ref "U$1") (pin "PA2") (pinfunction "PA2_PA2") (pintype "bidirectional"))
    )
    (net (code "61") (name "PA3") (class "Default")
      (node (ref "STM32F103_1") (pin "30") (pinfunction "PA9_30") (pintype "bidirectional"))
      (node (ref "U$1") (pin "PA3") (pinfunction "PA3_PA3") (pintype "bidirectional"))
    )
    (net (code "62") (name "PA9") (class "Default")
      (node (ref "ISP_COM") (pin "4") (pinfunction "4_4") (pintype "passive"))
      (node (ref "STM32F103_0") (pin "31") (pinfunction "PA10_31") (pintype "bidirectional"))
      (node (ref "U$1") (pin "PA9") (pinfunction "PA9_PA9") (pintype "bidirectional"))
    )
    (net (code "63") (name "PA10") (class "Default")
      (node (ref "ISP_COM") (pin "3") (pinfunction "3_3") (pintype "passive"))
      (node (ref "STM32F103_0") (pin "30") (pinfunction "PA9_30") (pintype "bidirectional"))
      (node (ref "U$1") (pin "PA10") (pinfunction "PA10_PA10") (pintype "bidirectional"))
    )
    (net (code "64") (name "PB6") (class "Default")
      (node (ref "MPU6050") (pin "23") (pinfunction "SCL_23") (pintype "bidirectional"))
      (node (ref "MPU_DEBUG") (pin "3") (pinfunction "3_3") (pintype "passive"))
      (node (ref "R2") (pin "1") (pinfunction "1_1") (pintype "passive"))
      (node (ref "U$1") (pin "PB6") (pinfunction "PB6_PB6") (pintype "bidirectional"))
    )
    (net (code "65") (name "PB7") (class "Default")
      (node (ref "MPU6050") (pin "24") (pinfunction "SDA_24") (pintype "bidirectional"))
      (node (ref "MPU_DEBUG") (pin "4") (pinfunction "4_4") (pintype "passive"))
      (node (ref "R1") (pin "1") (pinfunction "1_1") (pintype "passive"))
      (node (ref "U$1") (pin "PB7") (pinfunction "PB7_PB7") (pintype "bidirectional"))
    )
    (net (code "66") (name "SCK") (class "Default")
      (node (ref "SPI_NRF2401") (pin "5") (pinfunction "5_5") (pintype "passive"))
      (node (ref "STM32F103_0") (pin "15") (pinfunction "PA5_15") (pintype "bidirectional"))
    )
    (net (code "67") (name "unconnected-(3V3_0-ADJ{slash}GND-Pad1)") (class "Default")
      (node (ref "3V3_0") (pin "1") (pinfunction "ADJ/GND_1") (pintype "passive"))
    )
    (net (code "68") (name "unconnected-(3V3_1-ADJ{slash}GND-Pad1)") (class "Default")
      (node (ref "3V3_1") (pin "1") (pinfunction "ADJ/GND_1") (pintype "passive"))
    )
    (net (code "69") (name "unconnected-(MPU6050-AD0{slash}SDO-Pad9)") (class "Default")
      (node (ref "MPU6050") (pin "9") (pinfunction "AD0/SDO_9") (pintype "bidirectional"))
    )
    (net (code "70") (name "unconnected-(MPU6050-AUX_CL-Pad7)") (class "Default")
      (node (ref "MPU6050") (pin "7") (pinfunction "AUX_CL_7") (pintype "bidirectional"))
    )
    (net (code "71") (name "unconnected-(MPU6050-AUX_DA-Pad6)") (class "Default")
      (node (ref "MPU6050") (pin "6") (pinfunction "AUX_DA_6") (pintype "bidirectional"))
    )
    (net (code "72") (name "unconnected-(MPU6050-INT-Pad12)") (class "Default")
      (node (ref "MPU6050") (pin "12") (pinfunction "INT_12") (pintype "bidirectional"))
    )
    (net (code "73") (name "unconnected-(MPU6050-NC0-Pad2)") (class "Default")
      (node (ref "MPU6050") (pin "2") (pinfunction "NC0_2") (pintype "bidirectional"))
    )
    (net (code "74") (name "unconnected-(MPU6050-NC1-Pad3)") (class "Default")
      (node (ref "MPU6050") (pin "3") (pinfunction "NC1_3") (pintype "bidirectional"))
    )
    (net (code "75") (name "unconnected-(MPU6050-NC2-Pad4)") (class "Default")
      (node (ref "MPU6050") (pin "4") (pinfunction "NC2_4") (pintype "bidirectional"))
    )
    (net (code "76") (name "unconnected-(MPU6050-NC3-Pad5)") (class "Default")
      (node (ref "MPU6050") (pin "5") (pinfunction "NC3_5") (pintype "bidirectional"))
    )
    (net (code "77") (name "unconnected-(MPU6050-NC4-Pad14)") (class "Default")
      (node (ref "MPU6050") (pin "14") (pinfunction "NC4_14") (pintype "bidirectional"))
    )
    (net (code "78") (name "unconnected-(MPU6050-NC5-Pad15)") (class "Default")
      (node (ref "MPU6050") (pin "15") (pinfunction "NC5_15") (pintype "bidirectional"))
    )
    (net (code "79") (name "unconnected-(MPU6050-NC6-Pad16)") (class "Default")
      (node (ref "MPU6050") (pin "16") (pinfunction "NC6_16") (pintype "bidirectional"))
    )
    (net (code "80") (name "unconnected-(MPU6050-NC7-Pad17)") (class "Default")
      (node (ref "MPU6050") (pin "17") (pinfunction "NC7_17") (pintype "bidirectional"))
    )
    (net (code "81") (name "unconnected-(MPU6050-RESV0-Pad19)") (class "Default")
      (node (ref "MPU6050") (pin "19") (pinfunction "RESV0_19") (pintype "bidirectional"))
    )
    (net (code "82") (name "unconnected-(MPU6050-RESV1-Pad21)") (class "Default")
      (node (ref "MPU6050") (pin "21") (pinfunction "RESV1_21") (pintype "bidirectional"))
    )
    (net (code "83") (name "unconnected-(MPU6050-RESV2-Pad22)") (class "Default")
      (node (ref "MPU6050") (pin "22") (pinfunction "RESV2_22") (pintype "bidirectional"))
    )
    (net (code "84") (name "unconnected-(RST_BUTTON-Pad2)") (class "Default")
      (node (ref "RST_BUTTON") (pin "2") (pinfunction "2_2") (pintype "passive"))
    )
    (net (code "85") (name "unconnected-(RST_BUTTON-Pad3)") (class "Default")
      (node (ref "RST_BUTTON") (pin "3") (pinfunction "3_3") (pintype "passive"))
    )
    (net (code "86") (name "unconnected-(RST_BUTTON1-Pad2)") (class "Default")
      (node (ref "RST_BUTTON1") (pin "2") (pinfunction "2_2") (pintype "passive"))
    )
    (net (code "87") (name "unconnected-(RST_BUTTON1-Pad3)") (class "Default")
      (node (ref "RST_BUTTON1") (pin "3") (pinfunction "3_3") (pintype "passive"))
    )
    (net (code "88") (name "unconnected-(RST_BUTTON2-Pad2)") (class "Default")
      (node (ref "RST_BUTTON2") (pin "2") (pinfunction "2_2") (pintype "passive"))
    )
    (net (code "89") (name "unconnected-(RST_BUTTON2-Pad3)") (class "Default")
      (node (ref "RST_BUTTON2") (pin "3") (pinfunction "3_3") (pintype "passive"))
    )
    (net (code "90") (name "unconnected-(STM32F103_0-PA0_WKUP-Pad10)") (class "Default")
      (node (ref "STM32F103_0") (pin "10") (pinfunction "PA0_WKUP_10") (pintype "bidirectional"))
    )
    (net (code "91") (name "unconnected-(STM32F103_0-PA1-Pad11)") (class "Default")
      (node (ref "STM32F103_0") (pin "11") (pinfunction "PA1_11") (pintype "bidirectional"))
    )
    (net (code "92") (name "unconnected-(STM32F103_0-PA2-Pad12)") (class "Default")
      (node (ref "STM32F103_0") (pin "12") (pinfunction "PA2_12") (pintype "bidirectional"))
    )
    (net (code "93") (name "unconnected-(STM32F103_0-PA8-Pad29)") (class "Default")
      (node (ref "STM32F103_0") (pin "29") (pinfunction "PA8_29") (pintype "bidirectional"))
    )
    (net (code "94") (name "unconnected-(STM32F103_0-PA11-Pad32)") (class "Default")
      (node (ref "STM32F103_0") (pin "32") (pinfunction "PA11_32") (pintype "bidirectional"))
    )
    (net (code "95") (name "unconnected-(STM32F103_0-PA12-Pad33)") (class "Default")
      (node (ref "STM32F103_0") (pin "33") (pinfunction "PA12_33") (pintype "bidirectional"))
    )
    (net (code "96") (name "unconnected-(STM32F103_0-PA15-Pad38)") (class "Default")
      (node (ref "STM32F103_0") (pin "38") (pinfunction "PA15_38") (pintype "bidirectional"))
    )
    (net (code "97") (name "unconnected-(STM32F103_0-PB0-Pad18)") (class "Default")
      (node (ref "STM32F103_0") (pin "18") (pinfunction "PB0_18") (pintype "bidirectional"))
    )
    (net (code "98") (name "unconnected-(STM32F103_0-PB1-Pad19)") (class "Default")
      (node (ref "STM32F103_0") (pin "19") (pinfunction "PB1_19") (pintype "bidirectional"))
    )
    (net (code "99") (name "unconnected-(STM32F103_0-PB3-Pad39)") (class "Default")
      (node (ref "STM32F103_0") (pin "39") (pinfunction "PB3_39") (pintype "bidirectional"))
    )
    (net (code "100") (name "unconnected-(STM32F103_0-PB4-Pad40)") (class "Default")
      (node (ref "STM32F103_0") (pin "40") (pinfunction "PB4_40") (pintype "bidirectional"))
    )
    (net (code "101") (name "unconnected-(STM32F103_0-PB5-Pad41)") (class "Default")
      (node (ref "STM32F103_0") (pin "41") (pinfunction "PB5_41") (pintype "bidirectional"))
    )
    (net (code "102") (name "unconnected-(STM32F103_0-PB6-Pad42)") (class "Default")
      (node (ref "STM32F103_0") (pin "42") (pinfunction "PB6_42") (pintype "bidirectional"))
    )
    (net (code "103") (name "unconnected-(STM32F103_0-PB7-Pad43)") (class "Default")
      (node (ref "STM32F103_0") (pin "43") (pinfunction "PB7_43") (pintype "bidirectional"))
    )
    (net (code "104") (name "unconnected-(STM32F103_0-PB8-Pad45)") (class "Default")
      (node (ref "STM32F103_0") (pin "45") (pinfunction "PB8_45") (pintype "bidirectional"))
    )
    (net (code "105") (name "unconnected-(STM32F103_0-PB9-Pad46)") (class "Default")
      (node (ref "STM32F103_0") (pin "46") (pinfunction "PB9_46") (pintype "bidirectional"))
    )
    (net (code "106") (name "unconnected-(STM32F103_0-PB10-Pad21)") (class "Default")
      (node (ref "STM32F103_0") (pin "21") (pinfunction "PB10_21") (pintype "bidirectional"))
    )
    (net (code "107") (name "unconnected-(STM32F103_0-PB11-Pad22)") (class "Default")
      (node (ref "STM32F103_0") (pin "22") (pinfunction "PB11_22") (pintype "bidirectional"))
    )
    (net (code "108") (name "unconnected-(STM32F103_0-PB12-Pad25)") (class "Default")
      (node (ref "STM32F103_0") (pin "25") (pinfunction "PB12_25") (pintype "bidirectional"))
    )
    (net (code "109") (name "unconnected-(STM32F103_0-PB13-Pad26)") (class "Default")
      (node (ref "STM32F103_0") (pin "26") (pinfunction "PB13_26") (pintype "bidirectional"))
    )
    (net (code "110") (name "unconnected-(STM32F103_0-PB14-Pad27)") (class "Default")
      (node (ref "STM32F103_0") (pin "27") (pinfunction "PB14_27") (pintype "bidirectional"))
    )
    (net (code "111") (name "unconnected-(STM32F103_0-PB15-Pad28)") (class "Default")
      (node (ref "STM32F103_0") (pin "28") (pinfunction "PB15_28") (pintype "bidirectional"))
    )
    (net (code "112") (name "unconnected-(STM32F103_0-PC13_TAMPER_RTC-Pad2)") (class "Default")
      (node (ref "STM32F103_0") (pin "2") (pinfunction "PC13_TAMPER_RTC_2") (pintype "bidirectional"))
    )
    (net (code "113") (name "unconnected-(STM32F103_0-VBAT-Pad1)") (class "Default")
      (node (ref "STM32F103_0") (pin "1") (pinfunction "VBAT_1") (pintype "bidirectional"))
    )
    (net (code "114") (name "unconnected-(STM32F103_1-PA0_WKUP-Pad10)") (class "Default")
      (node (ref "STM32F103_1") (pin "10") (pinfunction "PA0_WKUP_10") (pintype "bidirectional"))
    )
    (net (code "115") (name "unconnected-(STM32F103_1-PA1-Pad11)") (class "Default")
      (node (ref "STM32F103_1") (pin "11") (pinfunction "PA1_11") (pintype "bidirectional"))
    )
    (net (code "116") (name "unconnected-(STM32F103_1-PA2-Pad12)") (class "Default")
      (node (ref "STM32F103_1") (pin "12") (pinfunction "PA2_12") (pintype "bidirectional"))
    )
    (net (code "117") (name "unconnected-(STM32F103_1-PA3-Pad13)") (class "Default")
      (node (ref "STM32F103_1") (pin "13") (pinfunction "PA3_13") (pintype "bidirectional"))
    )
    (net (code "118") (name "unconnected-(STM32F103_1-PA4-Pad14)") (class "Default")
      (node (ref "STM32F103_1") (pin "14") (pinfunction "PA4_14") (pintype "bidirectional"))
    )
    (net (code "119") (name "unconnected-(STM32F103_1-PA5-Pad15)") (class "Default")
      (node (ref "STM32F103_1") (pin "15") (pinfunction "PA5_15") (pintype "bidirectional"))
    )
    (net (code "120") (name "unconnected-(STM32F103_1-PA6-Pad16)") (class "Default")
      (node (ref "STM32F103_1") (pin "16") (pinfunction "PA6_16") (pintype "bidirectional"))
    )
    (net (code "121") (name "unconnected-(STM32F103_1-PA7-Pad17)") (class "Default")
      (node (ref "STM32F103_1") (pin "17") (pinfunction "PA7_17") (pintype "bidirectional"))
    )
    (net (code "122") (name "unconnected-(STM32F103_1-PA8-Pad29)") (class "Default")
      (node (ref "STM32F103_1") (pin "29") (pinfunction "PA8_29") (pintype "bidirectional"))
    )
    (net (code "123") (name "unconnected-(STM32F103_1-PA11-Pad32)") (class "Default")
      (node (ref "STM32F103_1") (pin "32") (pinfunction "PA11_32") (pintype "bidirectional"))
    )
    (net (code "124") (name "unconnected-(STM32F103_1-PA12-Pad33)") (class "Default")
      (node (ref "STM32F103_1") (pin "33") (pinfunction "PA12_33") (pintype "bidirectional"))
    )
    (net (code "125") (name "unconnected-(STM32F103_1-PA15-Pad38)") (class "Default")
      (node (ref "STM32F103_1") (pin "38") (pinfunction "PA15_38") (pintype "bidirectional"))
    )
    (net (code "126") (name "unconnected-(STM32F103_1-PB0-Pad18)") (class "Default")
      (node (ref "STM32F103_1") (pin "18") (pinfunction "PB0_18") (pintype "bidirectional"))
    )
    (net (code "127") (name "unconnected-(STM32F103_1-PB1-Pad19)") (class "Default")
      (node (ref "STM32F103_1") (pin "19") (pinfunction "PB1_19") (pintype "bidirectional"))
    )
    (net (code "128") (name "unconnected-(STM32F103_1-PB3-Pad39)") (class "Default")
      (node (ref "STM32F103_1") (pin "39") (pinfunction "PB3_39") (pintype "bidirectional"))
    )
    (net (code "129") (name "unconnected-(STM32F103_1-PB4-Pad40)") (class "Default")
      (node (ref "STM32F103_1") (pin "40") (pinfunction "PB4_40") (pintype "bidirectional"))
    )
    (net (code "130") (name "unconnected-(STM32F103_1-PB9-Pad46)") (class "Default")
      (node (ref "STM32F103_1") (pin "46") (pinfunction "PB9_46") (pintype "bidirectional"))
    )
    (net (code "131") (name "unconnected-(STM32F103_1-PB10-Pad21)") (class "Default")
      (node (ref "STM32F103_1") (pin "21") (pinfunction "PB10_21") (pintype "bidirectional"))
    )
    (net (code "132") (name "unconnected-(STM32F103_1-PB11-Pad22)") (class "Default")
      (node (ref "STM32F103_1") (pin "22") (pinfunction "PB11_22") (pintype "bidirectional"))
    )
    (net (code "133") (name "unconnected-(STM32F103_1-PB12-Pad25)") (class "Default")
      (node (ref "STM32F103_1") (pin "25") (pinfunction "PB12_25") (pintype "bidirectional"))
    )
    (net (code "134") (name "unconnected-(STM32F103_1-PB13-Pad26)") (class "Default")
      (node (ref "STM32F103_1") (pin "26") (pinfunction "PB13_26") (pintype "bidirectional"))
    )
    (net (code "135") (name "unconnected-(STM32F103_1-PB14-Pad27)") (class "Default")
      (node (ref "STM32F103_1") (pin "27") (pinfunction "PB14_27") (pintype "bidirectional"))
    )
    (net (code "136") (name "unconnected-(STM32F103_1-PB15-Pad28)") (class "Default")
      (node (ref "STM32F103_1") (pin "28") (pinfunction "PB15_28") (pintype "bidirectional"))
    )
    (net (code "137") (name "unconnected-(STM32F103_1-PC13_TAMPER_RTC-Pad2)") (class "Default")
      (node (ref "STM32F103_1") (pin "2") (pinfunction "PC13_TAMPER_RTC_2") (pintype "bidirectional"))
    )
    (net (code "138") (name "unconnected-(STM32F103_1-VBAT-Pad1)") (class "Default")
      (node (ref "STM32F103_1") (pin "1") (pinfunction "VBAT_1") (pintype "bidirectional"))
    )
    (net (code "139") (name "unconnected-(U$1-PadPA0)") (class "Default")
      (node (ref "U$1") (pin "PA0") (pinfunction "PA0_PA0") (pintype "bidirectional"))
    )
    (net (code "140") (name "unconnected-(U$1-PadPA1)") (class "Default")
      (node (ref "U$1") (pin "PA1") (pinfunction "PA1_PA1") (pintype "bidirectional"))
    )
    (net (code "141") (name "unconnected-(U$1-PadPA4)") (class "Default")
      (node (ref "U$1") (pin "PA4") (pinfunction "PA4_PA4") (pintype "bidirectional"))
    )
    (net (code "142") (name "unconnected-(U$1-PadPA8)") (class "Default")
      (node (ref "U$1") (pin "PA8") (pinfunction "PA8_PA8") (pintype "bidirectional"))
    )
    (net (code "143") (name "unconnected-(U$1-PadPA11)") (class "Default")
      (node (ref "U$1") (pin "PA11") (pinfunction "PA11_PA11") (pintype "bidirectional"))
    )
    (net (code "144") (name "unconnected-(U$1-PadPA12)") (class "Default")
      (node (ref "U$1") (pin "PA12") (pinfunction "PA12_PA12") (pintype "bidirectional"))
    )
    (net (code "145") (name "unconnected-(U$1-PadPA15)") (class "Default")
      (node (ref "U$1") (pin "PA15") (pinfunction "PA15_PA15") (pintype "bidirectional"))
    )
    (net (code "146") (name "unconnected-(U$1-PadPB0)") (class "Default")
      (node (ref "U$1") (pin "PB0") (pinfunction "PB0_PB0") (pintype "bidirectional"))
    )
    (net (code "147") (name "unconnected-(U$1-PadPB1)") (class "Default")
      (node (ref "U$1") (pin "PB1") (pinfunction "PB1_PB1") (pintype "bidirectional"))
    )
    (net (code "148") (name "unconnected-(U$1-PadPB3)") (class "Default")
      (node (ref "U$1") (pin "PB3") (pinfunction "PB3_PB3") (pintype "bidirectional"))
    )
    (net (code "149") (name "unconnected-(U$1-PadPB4)") (class "Default")
      (node (ref "U$1") (pin "PB4") (pinfunction "PB4_PB4") (pintype "bidirectional"))
    )
    (net (code "150") (name "unconnected-(U$1-PadPB5)") (class "Default")
      (node (ref "U$1") (pin "PB5") (pinfunction "PB5_PB5") (pintype "bidirectional"))
    )
    (net (code "151") (name "unconnected-(U$1-PadPB8)") (class "Default")
      (node (ref "U$1") (pin "PB8") (pinfunction "PB8_PB8") (pintype "bidirectional"))
    )
    (net (code "152") (name "unconnected-(U$1-PadPB9)") (class "Default")
      (node (ref "U$1") (pin "PB9") (pinfunction "PB9_PB9") (pintype "bidirectional"))
    )
    (net (code "153") (name "unconnected-(U$1-PadPB11)") (class "Default")
      (node (ref "U$1") (pin "PB11") (pinfunction "PB11_PB11") (pintype "bidirectional"))
    )
    (net (code "154") (name "unconnected-(U$1-PadPB12)") (class "Default")
      (node (ref "U$1") (pin "PB12") (pinfunction "PB12_PB12") (pintype "bidirectional"))
    )
    (net (code "155") (name "unconnected-(U$1-PadPB13)") (class "Default")
      (node (ref "U$1") (pin "PB13") (pinfunction "PB13_PB13") (pintype "bidirectional"))
    )
    (net (code "156") (name "unconnected-(U$1-PadPB14)") (class "Default")
      (node (ref "U$1") (pin "PB14") (pinfunction "PB14_PB14") (pintype "bidirectional"))
    )
    (net (code "157") (name "unconnected-(U$1-PadPB15)") (class "Default")
      (node (ref "U$1") (pin "PB15") (pinfunction "PB15_PB15") (pintype "bidirectional"))
    )
    (net (code "158") (name "unconnected-(U$1-PadPC0)") (class "Default")
      (node (ref "U$1") (pin "PC0") (pinfunction "PC0_PC0") (pintype "bidirectional"))
    )
    (net (code "159") (name "unconnected-(U$1-PadPC1)") (class "Default")
      (node (ref "U$1") (pin "PC1") (pinfunction "PC1_PC1") (pintype "bidirectional"))
    )
    (net (code "160") (name "unconnected-(U$1-PadPC6)") (class "Default")
      (node (ref "U$1") (pin "PC6") (pinfunction "PC6_PC6") (pintype "bidirectional"))
    )
    (net (code "161") (name "unconnected-(U$1-PadPC7)") (class "Default")
      (node (ref "U$1") (pin "PC7") (pinfunction "PC7_PC7") (pintype "bidirectional"))
    )
    (net (code "162") (name "unconnected-(U$1-PadPC13)") (class "Default")
      (node (ref "U$1") (pin "PC13") (pinfunction "PC13_PC13") (pintype "bidirectional"))
    )
    (net (code "163") (name "unconnected-(U$1-PadPD0)") (class "Default")
      (node (ref "U$1") (pin "PD0") (pinfunction "PD0_PD0") (pintype "bidirectional"))
    )
    (net (code "164") (name "unconnected-(U$1-PadPD1)") (class "Default")
      (node (ref "U$1") (pin "PD1") (pinfunction "PD1_PD1") (pintype "bidirectional"))
    )
    (net (code "165") (name "unconnected-(U$1-PadPD3)") (class "Default")
      (node (ref "U$1") (pin "PD3") (pinfunction "PD3_PD3") (pintype "bidirectional"))
    )
    (net (code "166") (name "unconnected-(U$1-PadPD4)") (class "Default")
      (node (ref "U$1") (pin "PD4") (pinfunction "PD4_PD4") (pintype "bidirectional"))
    )
    (net (code "167") (name "unconnected-(U$1-PadPD5)") (class "Default")
      (node (ref "U$1") (pin "PD5") (pinfunction "PD5_PD5") (pintype "bidirectional"))
    )
    (net (code "168") (name "unconnected-(U$1-PadPD6)") (class "Default")
      (node (ref "U$1") (pin "PD6") (pinfunction "PD6_PD6") (pintype "bidirectional"))
    )
    (net (code "169") (name "unconnected-(U$1-PadPD7)") (class "Default")
      (node (ref "U$1") (pin "PD7") (pinfunction "PD7_PD7") (pintype "bidirectional"))
    )
    (net (code "170") (name "unconnected-(U$1-PadPD8)") (class "Default")
      (node (ref "U$1") (pin "PD8") (pinfunction "PD8_PD8") (pintype "bidirectional"))
    )
    (net (code "171") (name "unconnected-(U$1-PadPD9)") (class "Default")
      (node (ref "U$1") (pin "PD9") (pinfunction "PD9_PD9") (pintype "bidirectional"))
    )
    (net (code "172") (name "unconnected-(U$1-PadPD10)") (class "Default")
      (node (ref "U$1") (pin "PD10") (pinfunction "PD10_PD10") (pintype "bidirectional"))
    )
    (net (code "173") (name "unconnected-(U$1-PadPD11)") (class "Default")
      (node (ref "U$1") (pin "PD11") (pinfunction "PD11_PD11") (pintype "bidirectional"))
    )
    (net (code "174") (name "unconnected-(U$1-PadPD12)") (class "Default")
      (node (ref "U$1") (pin "PD12") (pinfunction "PD12_PD12") (pintype "bidirectional"))
    )
    (net (code "175") (name "unconnected-(U$1-PadPD13)") (class "Default")
      (node (ref "U$1") (pin "PD13") (pinfunction "PD13_PD13") (pintype "bidirectional"))
    )
    (net (code "176") (name "unconnected-(U$1-PadPD14)") (class "Default")
      (node (ref "U$1") (pin "PD14") (pinfunction "PD14_PD14") (pintype "bidirectional"))
    )
    (net (code "177") (name "unconnected-(U$1-PadPD15)") (class "Default")
      (node (ref "U$1") (pin "PD15") (pinfunction "PD15_PD15") (pintype "bidirectional"))
    )
    (net (code "178") (name "unconnected-(U$1-PadPE0)") (class "Default")
      (node (ref "U$1") (pin "PE0") (pinfunction "PE0_PE0") (pintype "bidirectional"))
    )
    (net (code "179") (name "unconnected-(U$1-PadPE1)") (class "Default")
      (node (ref "U$1") (pin "PE1") (pinfunction "PE1_PE1") (pintype "bidirectional"))
    )
    (net (code "180") (name "unconnected-(U$1-PadPE2)") (class "Default")
      (node (ref "U$1") (pin "PE2") (pinfunction "PE2_PE2") (pintype "bidirectional"))
    )
    (net (code "181") (name "unconnected-(U$1-PadPE3)") (class "Default")
      (node (ref "U$1") (pin "PE3") (pinfunction "PE3_PE3") (pintype "bidirectional"))
    )
    (net (code "182") (name "unconnected-(U$1-PadPE4)") (class "Default")
      (node (ref "U$1") (pin "PE4") (pinfunction "PE4_PE4") (pintype "bidirectional"))
    )
    (net (code "183") (name "unconnected-(U$1-PadPE5)") (class "Default")
      (node (ref "U$1") (pin "PE5") (pinfunction "PE5_PE5") (pintype "bidirectional"))
    )
    (net (code "184") (name "unconnected-(U$1-PadPE6)") (class "Default")
      (node (ref "U$1") (pin "PE6") (pinfunction "PE6_PE6") (pintype "bidirectional"))
    )
    (net (code "185") (name "unconnected-(U$1-PadPE9)") (class "Default")
      (node (ref "U$1") (pin "PE9") (pinfunction "PE9_PE9") (pintype "bidirectional"))
    )
    (net (code "186") (name "unconnected-(U$1-PadPE10)") (class "Default")
      (node (ref "U$1") (pin "PE10") (pinfunction "PE10_PE10") (pintype "bidirectional"))
    )
    (net (code "187") (name "unconnected-(U$1-PadPE11)") (class "Default")
      (node (ref "U$1") (pin "PE11") (pinfunction "PE11_PE11") (pintype "bidirectional"))
    )
    (net (code "188") (name "unconnected-(U$1-PadPE12)") (class "Default")
      (node (ref "U$1") (pin "PE12") (pinfunction "PE12_PE12") (pintype "bidirectional"))
    )
    (net (code "189") (name "unconnected-(U$1-PadPE13)") (class "Default")
      (node (ref "U$1") (pin "PE13") (pinfunction "PE13_PE13") (pintype "bidirectional"))
    )
    (net (code "190") (name "unconnected-(U$1-PadPE14)") (class "Default")
      (node (ref "U$1") (pin "PE14") (pinfunction "PE14_PE14") (pintype "bidirectional"))
    )
    (net (code "191") (name "unconnected-(U$1-PadPE15)") (class "Default")
      (node (ref "U$1") (pin "PE15") (pinfunction "PE15_PE15") (pintype "bidirectional"))
    )
    (net (code "192") (name "unconnected-(U$1-PadVBAT)") (class "Default")
      (node (ref "U$1") (pin "VBAT") (pinfunction "VBAT_VBAT") (pintype "bidirectional"))
    )
  )
)
